# Oscillator_Counter.net
KiCad netlist of a schematic drawn in EAGLE
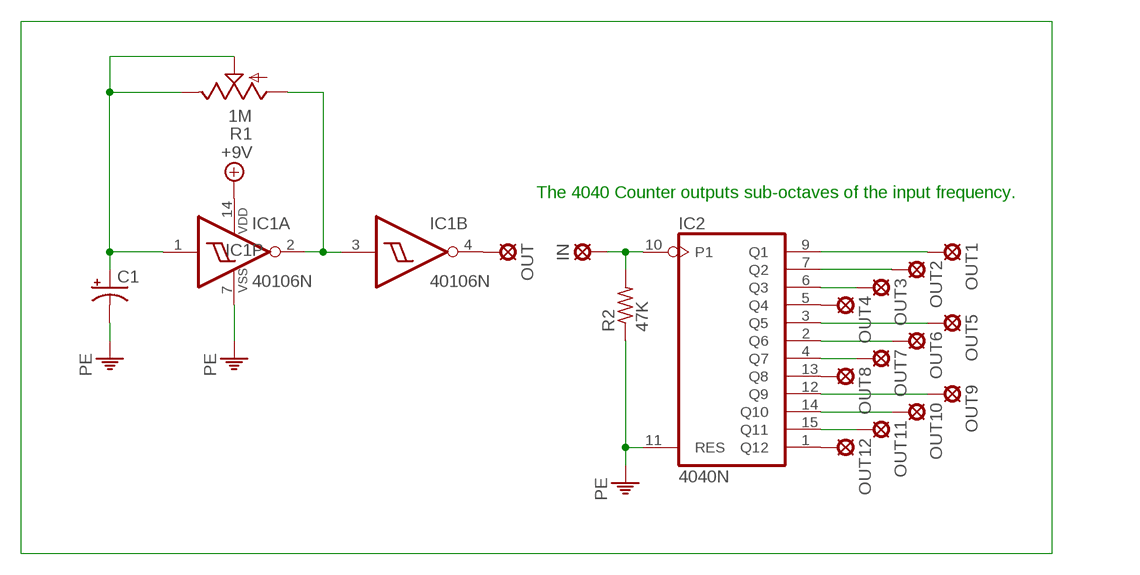
[diagram p0: schematic, sheet 1]

(export (version "E")
  (design (tool "Eeschema 10.0.6"))
  (components
    (comp (ref "C1")
      (value "CPOL-USE2,5-6E")
      (footprint "eagle-import:E2,5-6E")
      (libsource (lib "eagle-import") (part "CPOL-USE2,5-6E"))
    )
    (comp (ref "IC1")
      (value "40106N")
      (footprint "eagle-import:DIL14")
      (libsource (lib "eagle-import") (part "40106N"))
    )
    (comp (ref "IC2")
      (value "4040N")
      (footprint "eagle-import:DIL16")
      (libsource (lib "eagle-import") (part "4040N"))
    )
    (comp (ref "IN")
      (value "MCS10B")
      (footprint "eagle-import:MCS10B")
      (libsource (lib "eagle-import") (part "MCS10B"))
    )
    (comp (ref "OUT")
      (value "MCS10B")
      (footprint "eagle-import:MCS10B")
      (libsource (lib "eagle-import") (part "MCS10B"))
    )
    (comp (ref "OUT1")
      (value "MCS10B")
      (footprint "eagle-import:MCS10B")
      (libsource (lib "eagle-import") (part "MCS10B"))
    )
    (comp (ref "OUT2")
      (value "MCS10B")
      (footprint "eagle-import:MCS10B")
      (libsource (lib "eagle-import") (part "MCS10B"))
    )
    (comp (ref "OUT3")
      (value "MCS10B")
      (footprint "eagle-import:MCS10B")
      (libsource (lib "eagle-import") (part "MCS10B"))
    )
    (comp (ref "OUT4")
      (value "MCS10B")
      (footprint "eagle-import:MCS10B")
      (libsource (lib "eagle-import") (part "MCS10B"))
    )
    (comp (ref "OUT5")
      (value "MCS10B")
      (footprint "eagle-import:MCS10B")
      (libsource (lib "eagle-import") (part "MCS10B"))
    )
    (comp (ref "OUT6")
      (value "MCS10B")
      (footprint "eagle-import:MCS10B")
      (libsource (lib "eagle-import") (part "MCS10B"))
    )
    (comp (ref "OUT7")
      (value "MCS10B")
      (footprint "eagle-import:MCS10B")
      (libsource (lib "eagle-import") (part "MCS10B"))
    )
    (comp (ref "OUT8")
      (value "MCS10B")
      (footprint "eagle-import:MCS10B")
      (libsource (lib "eagle-import") (part "MCS10B"))
    )
    (comp (ref "OUT9")
      (value "MCS10B")
      (footprint "eagle-import:MCS10B")
      (libsource (lib "eagle-import") (part "MCS10B"))
    )
    (comp (ref "OUT10")
      (value "MCS10B")
      (footprint "eagle-import:MCS10B")
      (libsource (lib "eagle-import") (part "MCS10B"))
    )
    (comp (ref "OUT11")
      (value "MCS10B")
      (footprint "eagle-import:MCS10B")
      (libsource (lib "eagle-import") (part "MCS10B"))
    )
    (comp (ref "OUT12")
      (value "MCS10B")
      (footprint "eagle-import:MCS10B")
      (libsource (lib "eagle-import") (part "MCS10B"))
    )
    (comp (ref "R1")
      (value "1M")
      (footprint "eagle-import:EVUF")
      (libsource (lib "eagle-import") (part "US-EVUAF2"))
    )
    (comp (ref "R2")
      (value "47K")
      (footprint "eagle-import:0204_7")
      (libsource (lib "eagle-import") (part "R-US_0204/7"))
    )
  )
  (nets
    (net (code "1") (name "+9V") (class "Default")
      (node (ref "IC1") (pin "14") (pinfunction "VDD_14") (pintype "power_in"))
    )
    (net (code "2") (name "Net-(IC1A-I)") (class "Default")
      (node (ref "C1") (pin "+") (pinfunction "+_+") (pintype "passive"))
      (node (ref "IC1") (pin "1") (pinfunction "I_1") (pintype "input"))
      (node (ref "R1") (pin "2") (pinfunction "S_2") (pintype "passive"))
      (node (ref "R1") (pin "3") (pinfunction "E_3") (pintype "passive"))
    )
    (net (code "3") (name "Net-(IC1A-O)") (class "Default")
      (node (ref "IC1") (pin "2") (pinfunction "O_2") (pintype "output"))
      (node (ref "IC1") (pin "3") (pinfunction "I_3") (pintype "input"))
      (node (ref "R1") (pin "1") (pinfunction "A_1") (pintype "passive"))
    )
    (net (code "4") (name "Net-(IC1B-O)") (class "Default")
      (node (ref "IC1") (pin "4") (pinfunction "O_4") (pintype "output"))
      (node (ref "OUT") (pin "MP") (pinfunction "MP_MP") (pintype "passive"))
    )
    (net (code "5") (name "Net-(IC2A-P1)") (class "Default")
      (node (ref "IC2") (pin "10") (pinfunction "P1_10") (pintype "input"))
      (node (ref "IN") (pin "MP") (pinfunction "MP_MP") (pintype "passive"))
      (node (ref "R2") (pin "2") (pinfunction "2_2") (pintype "passive"))
    )
    (net (code "6") (name "Net-(IC2A-Q1)") (class "Default")
      (node (ref "IC2") (pin "9") (pinfunction "Q1_9") (pintype "output"))
      (node (ref "OUT1") (pin "MP") (pinfunction "MP_MP") (pintype "passive"))
    )
    (net (code "7") (name "Net-(IC2A-Q2)") (class "Default")
      (node (ref "IC2") (pin "7") (pinfunction "Q2_7") (pintype "output"))
      (node (ref "OUT2") (pin "MP") (pinfunction "MP_MP") (pintype "passive"))
    )
    (net (code "8") (name "Net-(IC2A-Q3)") (class "Default")
      (node (ref "IC2") (pin "6") (pinfunction "Q3_6") (pintype "output"))
      (node (ref "OUT3") (pin "MP") (pinfunction "MP_MP") (pintype "passive"))
    )
    (net (code "9") (name "Net-(IC2A-Q4)") (class "Default")
      (node (ref "IC2") (pin "5") (pinfunction "Q4_5") (pintype "output"))
      (node (ref "OUT4") (pin "MP") (pinfunction "MP_MP") (pintype "passive"))
    )
    (net (code "10") (name "Net-(IC2A-Q5)") (class "Default")
      (node (ref "IC2") (pin "3") (pinfunction "Q5_3") (pintype "output"))
      (node (ref "OUT5") (pin "MP") (pinfunction "MP_MP") (pintype "passive"))
    )
    (net (code "11") (name "Net-(IC2A-Q6)") (class "Default")
      (node (ref "IC2") (pin "2") (pinfunction "Q6_2") (pintype "output"))
      (node (ref "OUT6") (pin "MP") (pinfunction "MP_MP") (pintype "passive"))
    )
    (net (code "12") (name "Net-(IC2A-Q7)") (class "Default")
      (node (ref "IC2") (pin "4") (pinfunction "Q7_4") (pintype "output"))
      (node (ref "OUT7") (pin "MP") (pinfunction "MP_MP") (pintype "passive"))
    )
    (net (code "13") (name "Net-(IC2A-Q8)") (class "Default")
      (node (ref "IC2") (pin "13") (pinfunction "Q8_13") (pintype "output"))
      (node (ref "OUT8") (pin "MP") (pinfunction "MP_MP") (pintype "passive"))
    )
    (net (code "14") (name "Net-(IC2A-Q9)") (class "Default")
      (node (ref "IC2") (pin "12") (pinfunction "Q9_12") (pintype "output"))
      (node (ref "OUT9") (pin "MP") (pinfunction "MP_MP") (pintype "passive"))
    )
    (net (code "15") (name "Net-(IC2A-Q10)") (class "Default")
      (node (ref "IC2") (pin "14") (pinfunction "Q10_14") (pintype "output"))
      (node (ref "OUT10") (pin "MP") (pinfunction "MP_MP") (pintype "passive"))
    )
    (net (code "16") (name "Net-(IC2A-Q11)") (class "Default")
      (node (ref "IC2") (pin "15") (pinfunction "Q11_15") (pintype "output"))
      (node (ref "OUT11") (pin "MP") (pinfunction "MP_MP") (pintype "passive"))
    )
    (net (code "17") (name "Net-(IC2A-Q12)") (class "Default")
      (node (ref "IC2") (pin "1") (pinfunction "Q12_1") (pintype "output"))
      (node (ref "OUT12") (pin "MP") (pinfunction "MP_MP") (pintype "passive"))
    )
    (net (code "18") (name "PE") (class "Default")
      (node (ref "C1") (pin "-") (pinfunction "-_-") (pintype "passive"))
      (node (ref "IC1") (pin "7") (pinfunction "VSS_7") (pintype "power_in"))
      (node (ref "IC2") (pin "11") (pinfunction "RES_11") (pintype "input"))
      (node (ref "R2") (pin "1") (pinfunction "1_1") (pintype "passive"))
    )
  )
)
